# 8Vregulator.net
KiCad netlist of a schematic drawn in EasyEDA
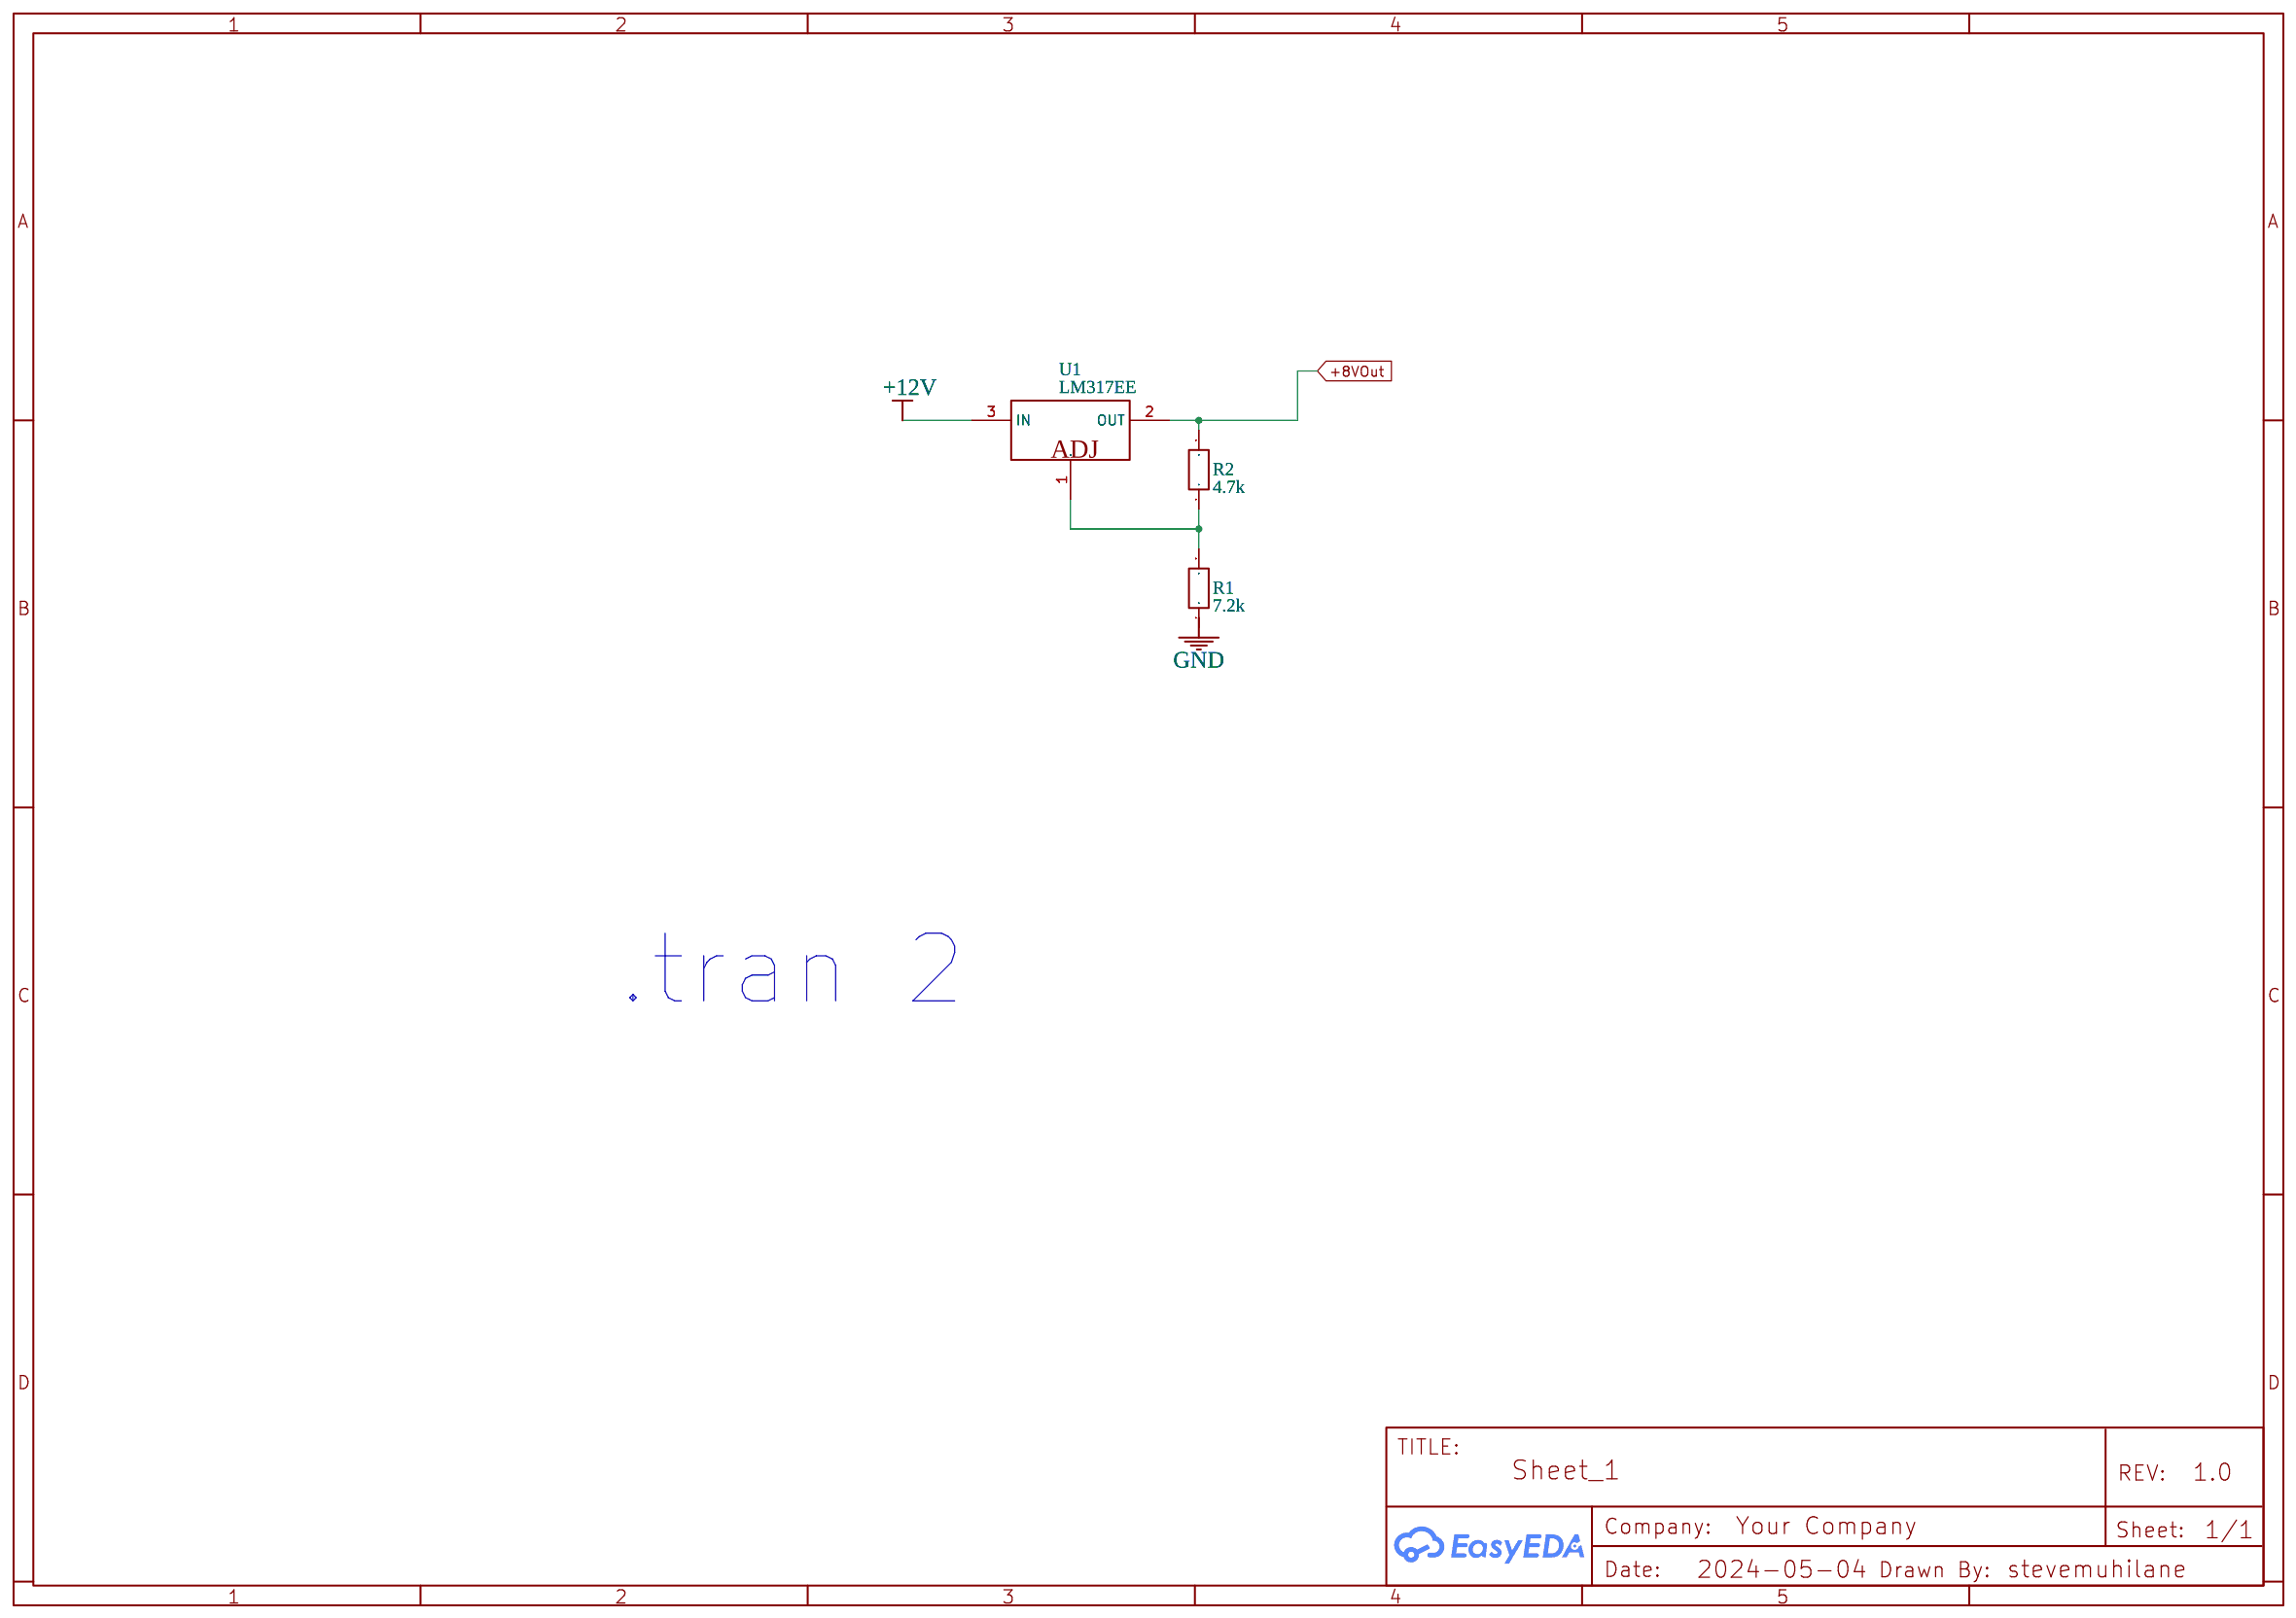
[diagram p0: schematic sheet]

(export (version "E")
  (design (tool "Eeschema 10.0.6"))
  (components
    (comp (ref "R1") (value "7.2k") (libsource (lib "") (part "Resistor_EU")))
    (comp (ref "R2") (value "4.7k") (libsource (lib "") (part "Resistor_EU")))
    (comp (ref "U1") (value "LM317EE") (libsource (lib "") (part "LM317")))
  )
  (nets
    (net (code "1") (name "+8VOut") (class "Default")
      (node (ref "R2") (pin "2") (pinfunction "2_2") (pintype "unspecified"))
      (node (ref "U1") (pin "2") (pinfunction "OUT_2") (pintype "passive"))
    )
    (net (code "2") (name "+12V") (class "Default")
      (node (ref "U1") (pin "3") (pinfunction "IN_3") (pintype "passive"))
    )
    (net (code "4") (name "Net-(U1-ADJ)") (class "Default")
      (node (ref "R1") (pin "2") (pinfunction "2_2") (pintype "unspecified"))
      (node (ref "R2") (pin "1") (pinfunction "1_1") (pintype "unspecified"))
      (node (ref "U1") (pin "1") (pinfunction "ADJ_1") (pintype "unspecified"))
    )
    (net (code "5") (name "unconnected-(R1-Pad1)") (class "Default")
      (node (ref "R1") (pin "1") (pinfunction "1_1") (pintype "unspecified"))
    )
  )
)
